# pc_healthypi_move_sensor_dual_v1.net
KiCad netlist of a schematic drawn in EAGLE
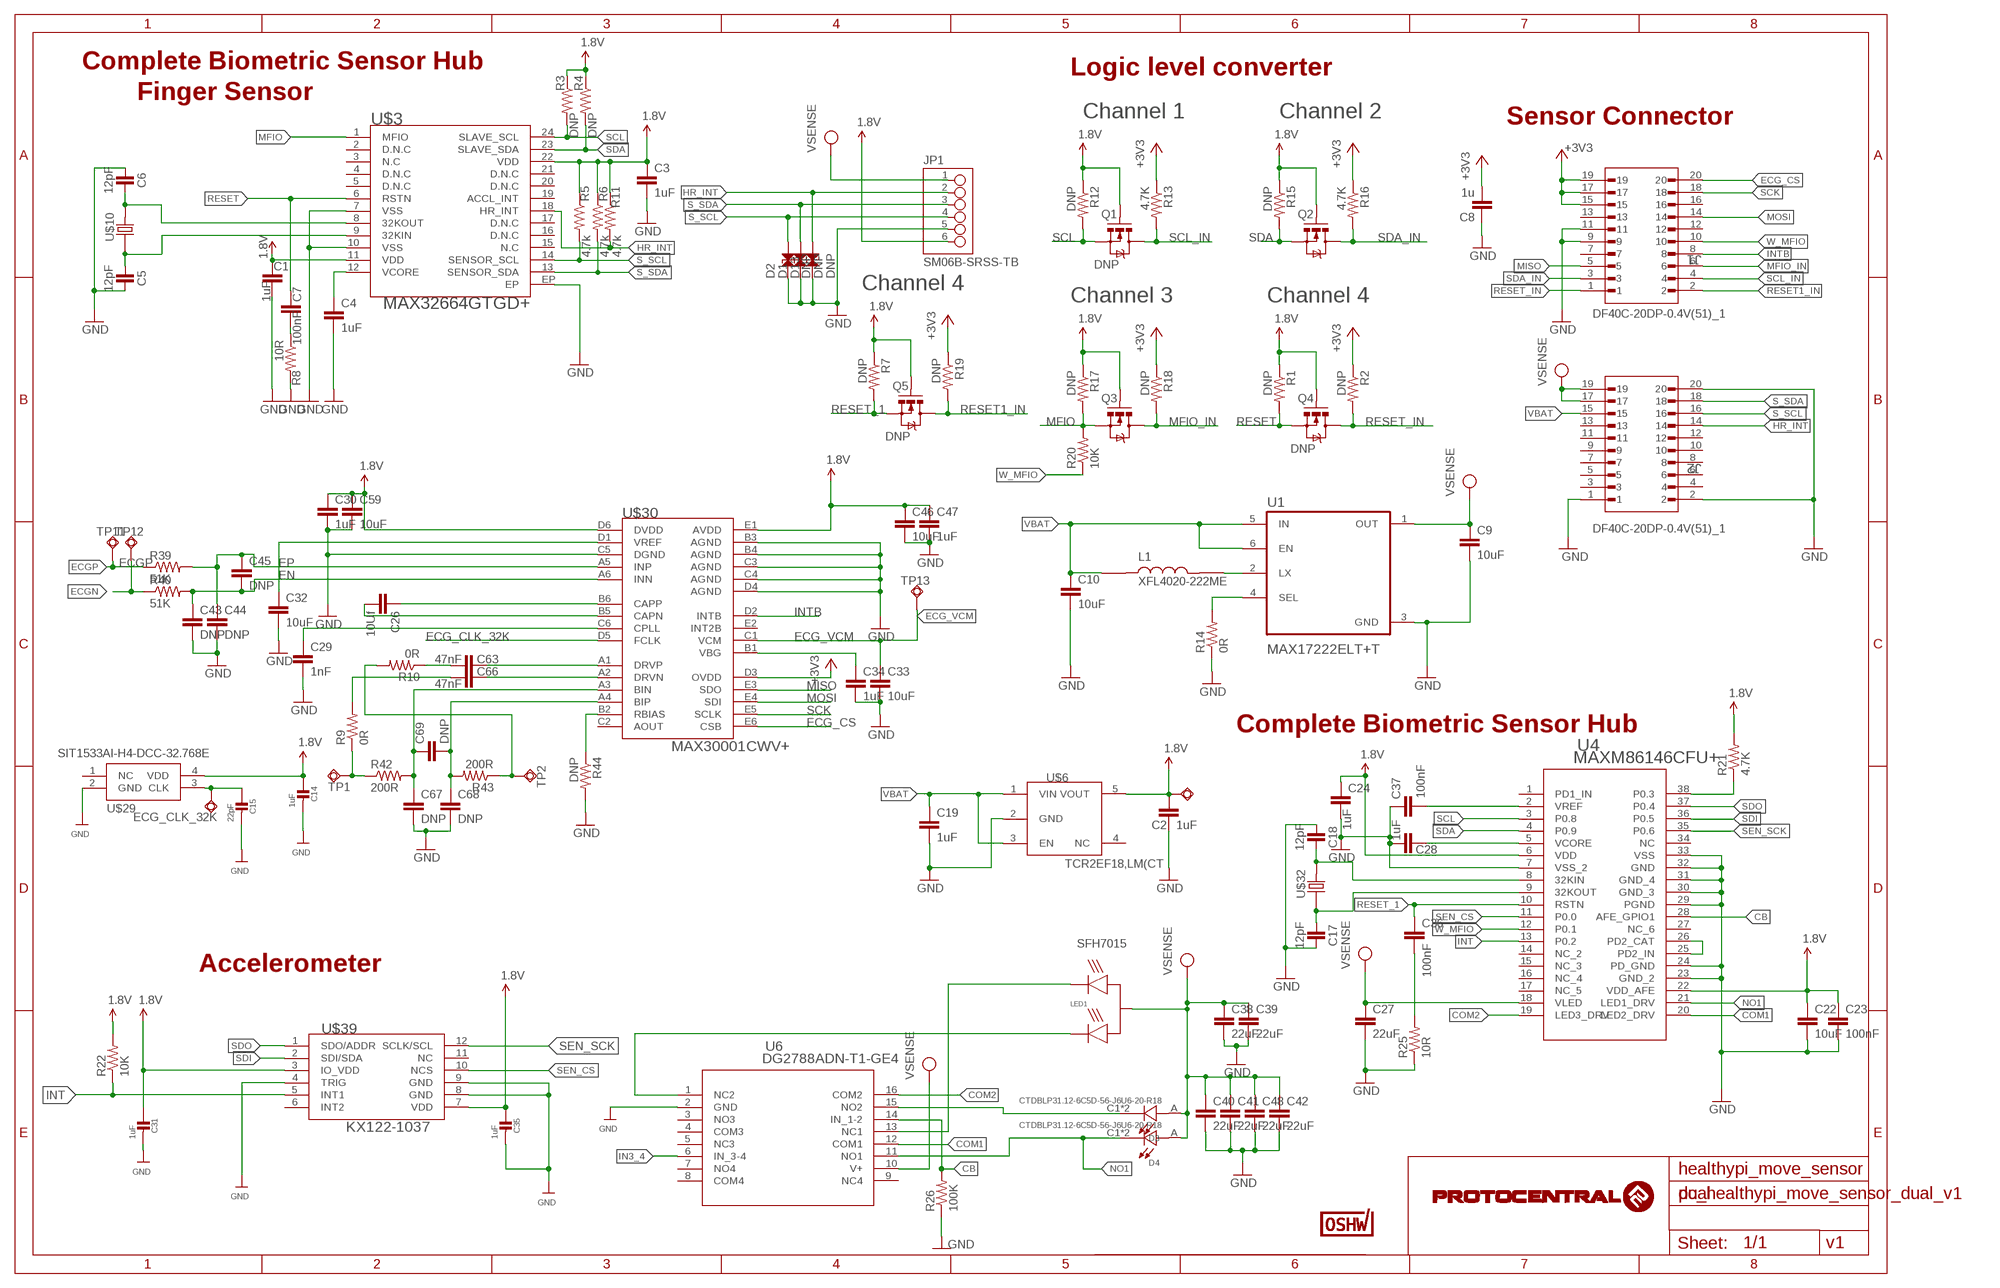
[diagram p0: schematic, sheet 1]

(export (version "E")
  (design (tool "Eeschema 10.0.6"))
  (components
    (comp (ref "C1")
      (value "1uF")
      (footprint "eagle-import:C0402")
      (libsource (lib "eagle-import") (part "C-EUC0402"))
    )
    (comp (ref "C2")
      (value "1uF")
      (footprint "eagle-import:C0402")
      (libsource (lib "eagle-import") (part "C-EUC0402"))
    )
    (comp (ref "C3")
      (value "1uF")
      (footprint "eagle-import:C0402")
      (libsource (lib "eagle-import") (part "C-EUC0402"))
    )
    (comp (ref "C4")
      (value "1uF")
      (footprint "eagle-import:C0402")
      (libsource (lib "eagle-import") (part "C-EUC0402"))
    )
    (comp (ref "C5")
      (value "12pF")
      (footprint "eagle-import:C0402")
      (libsource (lib "eagle-import") (part "CAPACITORS-0402"))
    )
    (comp (ref "C6")
      (value "12pF")
      (footprint "eagle-import:C0402")
      (libsource (lib "eagle-import") (part "CAPACITORS-0402"))
    )
    (comp (ref "C7")
      (value "100nF")
      (footprint "eagle-import:C0402")
      (libsource (lib "eagle-import") (part "C-EUC0402"))
    )
    (comp (ref "C8")
      (value "1u")
      (footprint "eagle-import:C0402")
      (libsource (lib "eagle-import") (part "C-EUC0402"))
    )
    (comp (ref "C9")
      (value "10uF")
      (footprint "eagle-import:C0402")
      (libsource (lib "eagle-import") (part "C-EUC0402"))
    )
    (comp (ref "C10")
      (value "10uF")
      (footprint "eagle-import:C0402")
      (libsource (lib "eagle-import") (part "C-EUC0402"))
    )
    (comp (ref "C14")
      (value "1uF")
      (footprint "eagle-import:0402")
      (libsource (lib "eagle-import") (part "CAP_CERAMIC0402"))
    )
    (comp (ref "C15")
      (value "22pF")
      (footprint "eagle-import:0402")
      (libsource (lib "eagle-import") (part "CAP_CERAMIC0402"))
    )
    (comp (ref "C17")
      (value "12pF")
      (footprint "eagle-import:C0402")
      (libsource (lib "eagle-import") (part "CAPACITORS-0402"))
    )
    (comp (ref "C18")
      (value "12pF")
      (footprint "eagle-import:C0402")
      (libsource (lib "eagle-import") (part "CAPACITORS-0402"))
    )
    (comp (ref "C19")
      (value "1uF")
      (footprint "eagle-import:C0402")
      (libsource (lib "eagle-import") (part "C-EUC0402"))
    )
    (comp (ref "C22")
      (value "10uF")
      (footprint "eagle-import:C0402")
      (libsource (lib "eagle-import") (part "C-EUC0402"))
    )
    (comp (ref "C23")
      (value "100nF")
      (footprint "eagle-import:C0402")
      (libsource (lib "eagle-import") (part "C-EUC0402"))
    )
    (comp (ref "C24")
      (value "1uF")
      (footprint "eagle-import:C0402")
      (libsource (lib "eagle-import") (part "C-EUC0402"))
    )
    (comp (ref "C26")
      (value "10Uf")
      (footprint "eagle-import:C0402")
      (libsource (lib "eagle-import") (part "C-EUC0402"))
    )
    (comp (ref "C27")
      (value "22uF")
      (footprint "eagle-import:C0805")
      (libsource (lib "eagle-import") (part "C-EUC0805"))
    )
    (comp (ref "C28")
      (value "1uF")
      (footprint "eagle-import:C0402")
      (libsource (lib "eagle-import") (part "C-EUC0402"))
    )
    (comp (ref "C29")
      (value "1nF")
      (footprint "eagle-import:C0402")
      (libsource (lib "eagle-import") (part "C-EUC0402"))
    )
    (comp (ref "C30")
      (value "1uF")
      (footprint "eagle-import:C0402")
      (libsource (lib "eagle-import") (part "C-EUC0402"))
    )
    (comp (ref "C31")
      (value "1uF")
      (footprint "eagle-import:0402")
      (libsource (lib "eagle-import") (part "CAP_CERAMIC0402"))
    )
    (comp (ref "C32")
      (value "10uF")
      (footprint "eagle-import:C0402")
      (libsource (lib "eagle-import") (part "C-EUC0402"))
    )
    (comp (ref "C33")
      (value "10uF")
      (footprint "eagle-import:C0402")
      (libsource (lib "eagle-import") (part "C-EUC0402"))
    )
    (comp (ref "C34")
      (value "1uF")
      (footprint "eagle-import:C0402")
      (libsource (lib "eagle-import") (part "C-EUC0402"))
    )
    (comp (ref "C35")
      (value "1uF")
      (footprint "eagle-import:0402")
      (libsource (lib "eagle-import") (part "CAP_CERAMIC0402"))
    )
    (comp (ref "C36")
      (value "100nF")
      (footprint "eagle-import:C0402")
      (libsource (lib "eagle-import") (part "C-EUC0402"))
    )
    (comp (ref "C37")
      (value "100nF")
      (footprint "eagle-import:C0402")
      (libsource (lib "eagle-import") (part "C-EUC0402"))
    )
    (comp (ref "C38")
      (value "22uF")
      (footprint "eagle-import:C0805")
      (libsource (lib "eagle-import") (part "C-EUC0805"))
    )
    (comp (ref "C39")
      (value "22uF")
      (footprint "eagle-import:C0805")
      (libsource (lib "eagle-import") (part "C-EUC0805"))
    )
    (comp (ref "C40")
      (value "22uF")
      (footprint "eagle-import:C0805")
      (libsource (lib "eagle-import") (part "C-EUC0805"))
    )
    (comp (ref "C41")
      (value "22uF")
      (footprint "eagle-import:C0805")
      (libsource (lib "eagle-import") (part "C-EUC0805"))
    )
    (comp (ref "C42")
      (value "22uF")
      (footprint "eagle-import:C0805")
      (libsource (lib "eagle-import") (part "C-EUC0805"))
    )
    (comp (ref "C43")
      (value "DNP")
      (footprint "eagle-import:C0402")
      (libsource (lib "eagle-import") (part "C-EUC0402"))
    )
    (comp (ref "C44")
      (value "DNP")
      (footprint "eagle-import:C0402")
      (libsource (lib "eagle-import") (part "C-EUC0402"))
    )
    (comp (ref "C45")
      (value "DNP")
      (footprint "eagle-import:C0402")
      (libsource (lib "eagle-import") (part "C-EUC0402"))
    )
    (comp (ref "C46")
      (value "10uF")
      (footprint "eagle-import:C0402")
      (libsource (lib "eagle-import") (part "C-EUC0402"))
    )
    (comp (ref "C47")
      (value "1uF")
      (footprint "eagle-import:C0402")
      (libsource (lib "eagle-import") (part "C-EUC0402"))
    )
    (comp (ref "C48")
      (value "22uF")
      (footprint "eagle-import:C0805")
      (libsource (lib "eagle-import") (part "C-EUC0805"))
    )
    (comp (ref "C59")
      (value "10uF")
      (footprint "eagle-import:C0402")
      (libsource (lib "eagle-import") (part "C-EUC0402"))
    )
    (comp (ref "C63")
      (value "47nF")
      (footprint "eagle-import:C0402")
      (libsource (lib "eagle-import") (part "C-EUC0402"))
    )
    (comp (ref "C66")
      (value "47nF")
      (footprint "eagle-import:C0402")
      (libsource (lib "eagle-import") (part "C-EUC0402"))
    )
    (comp (ref "C67")
      (value "DNP")
      (footprint "eagle-import:C0402")
      (libsource (lib "eagle-import") (part "C-EUC0402"))
    )
    (comp (ref "C68")
      (value "DNP")
      (footprint "eagle-import:C0402")
      (libsource (lib "eagle-import") (part "C-EUC0402"))
    )
    (comp (ref "C69")
      (value "DNP")
      (footprint "eagle-import:C0402")
      (libsource (lib "eagle-import") (part "C-EUC0402"))
    )
    (comp (ref "D1")
      (value "DNP")
      (footprint "eagle-import:0402")
      (fields
        (field (name "DIGIKEY_PART") "PESD0402-140CT-ND")
        (field (name "MOUSE_PART") "650-PESD0402-140")
      )
      (libsource (lib "eagle-import") (part "PESD0402-0402"))
    )
    (comp (ref "D2")
      (value "DNP")
      (footprint "eagle-import:0402")
      (fields
        (field (name "DIGIKEY_PART") "PESD0402-140CT-ND")
        (field (name "MOUSE_PART") "650-PESD0402-140")
      )
      (libsource (lib "eagle-import") (part "PESD0402-0402"))
    )
    (comp (ref "D3")
      (value "CTDBLP31.12-6C5D-56-J6U6-20-R18")
      (footprint "eagle-import:LED_CTDBLP31.12-6C5D-56-J6U6-20-R18")
      (fields
        (field (name "MF") "OSRAM Opto Semiconductors")
        (field (name "MP") "CT DBLP31.12-6C5D-56-J6U6-20-R18")
      )
      (libsource (lib "eagle-import") (part "CTDBLP31.12-6C5D-56-J6U6-20-R18"))
    )
    (comp (ref "D4")
      (value "CTDBLP31.12-6C5D-56-J6U6-20-R18")
      (footprint "eagle-import:LED_CTDBLP31.12-6C5D-56-J6U6-20-R18")
      (fields
        (field (name "MF") "OSRAM Opto Semiconductors")
        (field (name "MP") "CT DBLP31.12-6C5D-56-J6U6-20-R18")
      )
      (libsource (lib "eagle-import") (part "CTDBLP31.12-6C5D-56-J6U6-20-R18"))
    )
    (comp (ref "D13")
      (value "DNP")
      (footprint "eagle-import:0402")
      (fields
        (field (name "DIGIKEY_PART") "PESD0402-140CT-ND")
        (field (name "MOUSE_PART") "650-PESD0402-140")
      )
      (libsource (lib "eagle-import") (part "PESD0402-0402"))
    )
    (comp (ref "J1")
      (value "DF40C-20DP-0.4V(51)_1")
      (footprint "eagle-import:HRS_DF40C-20DP-0.4V(51)")
      (fields (field (name "MANUFACTURER") "Hirose Electric"))
      (libsource (lib "eagle-import") (part "DF40C-20DP-0.4V(51)_1"))
    )
    (comp (ref "J2")
      (value "DF40C-20DP-0.4V(51)_1")
      (footprint "eagle-import:HRS_DF40C-20DP-0.4V(51)")
      (fields (field (name "MANUFACTURER") "Hirose Electric"))
      (libsource (lib "eagle-import") (part "DF40C-20DP-0.4V(51)_1"))
    )
    (comp (ref "JP1")
      (value "SM06B-SRSS-TB")
      (footprint "eagle-import:SM06B-SRSS-TB")
      (fields (field (name "MF") "JST Sales"))
      (libsource (lib "eagle-import") (part "SM06B-SRSS-TB"))
    )
    (comp (ref "L1")
      (value "XFL4020-222ME")
      (footprint "eagle-import:IND_XFL4020-222ME")
      (fields (field (name "MF") "Coilcraft"))
      (libsource (lib "eagle-import") (part "XFL4020-222ME"))
    )
    (comp (ref "LED1")
      (value "SFH7015")
      (footprint "eagle-import:SFH7015")
      (fields (field (name "MF") "OSRAM Opto Semiconductors") (field (name "MP") "SFH 7015"))
      (libsource (lib "eagle-import") (part "SFH7015"))
    )
    (comp (ref "Q1")
      (value "DNP")
      (footprint "eagle-import:SOT23-3")
      (libsource (lib "eagle-import") (part "MOSFET-NCHANNELSMD"))
    )
    (comp (ref "Q2")
      (value "DNP")
      (footprint "eagle-import:SOT23-3")
      (libsource (lib "eagle-import") (part "MOSFET-NCHANNELSMD"))
    )
    (comp (ref "Q3")
      (value "DNP")
      (footprint "eagle-import:SOT23-3")
      (libsource (lib "eagle-import") (part "MOSFET-NCHANNELSMD"))
    )
    (comp (ref "Q4")
      (value "DNP")
      (footprint "eagle-import:SOT23-3")
      (libsource (lib "eagle-import") (part "MOSFET-NCHANNELSMD"))
    )
    (comp (ref "Q5")
      (value "DNP")
      (footprint "eagle-import:SOT23-3")
      (libsource (lib "eagle-import") (part "MOSFET-NCHANNELSMD"))
    )
    (comp (ref "R1")
      (value "DNP")
      (footprint "eagle-import:0402-RES")
      (libsource (lib "eagle-import") (part "RESISTOR0402-RES"))
    )
    (comp (ref "R2")
      (value "DNP")
      (footprint "eagle-import:0402-RES")
      (libsource (lib "eagle-import") (part "RESISTOR0402-RES"))
    )
    (comp (ref "R3")
      (value "DNP")
      (footprint "eagle-import:0402-RES")
      (libsource (lib "eagle-import") (part "RESISTOR0402-RES"))
    )
    (comp (ref "R4")
      (value "DNP")
      (footprint "eagle-import:0402-RES")
      (libsource (lib "eagle-import") (part "RESISTOR0402-RES"))
    )
    (comp (ref "R5")
      (value "4.7k")
      (footprint "eagle-import:0402-RES")
      (libsource (lib "eagle-import") (part "RESISTOR0402-RES"))
    )
    (comp (ref "R6")
      (value "4.7k")
      (footprint "eagle-import:0402-RES")
      (libsource (lib "eagle-import") (part "RESISTOR0402-RES"))
    )
    (comp (ref "R7")
      (value "DNP")
      (footprint "eagle-import:0402-RES")
      (libsource (lib "eagle-import") (part "RESISTOR0402-RES"))
    )
    (comp (ref "R8")
      (value "10R")
      (footprint "eagle-import:0402-RES")
      (libsource (lib "eagle-import") (part "RESISTOR0402-RES"))
    )
    (comp (ref "R9")
      (value "0R")
      (footprint "eagle-import:0402-RES")
      (libsource (lib "eagle-import") (part "RESISTOR0402-RES"))
    )
    (comp (ref "R10")
      (value "0R")
      (footprint "eagle-import:0402-RES")
      (libsource (lib "eagle-import") (part "RESISTOR0402-RES"))
    )
    (comp (ref "R11")
      (value "4.7k")
      (footprint "eagle-import:0402-RES")
      (libsource (lib "eagle-import") (part "RESISTOR0402-RES"))
    )
    (comp (ref "R12")
      (value "DNP")
      (footprint "eagle-import:0402-RES")
      (libsource (lib "eagle-import") (part "RESISTOR0402-RES"))
    )
    (comp (ref "R13")
      (value "4.7K")
      (footprint "eagle-import:0402-RES")
      (libsource (lib "eagle-import") (part "RESISTOR0402-RES"))
    )
    (comp (ref "R14")
      (value "0R")
      (footprint "eagle-import:R0402")
      (libsource (lib "eagle-import") (part "R-US_R0402"))
    )
    (comp (ref "R15")
      (value "DNP")
      (footprint "eagle-import:0402-RES")
      (libsource (lib "eagle-import") (part "RESISTOR0402-RES"))
    )
    (comp (ref "R16")
      (value "4.7K")
      (footprint "eagle-import:0402-RES")
      (libsource (lib "eagle-import") (part "RESISTOR0402-RES"))
    )
    (comp (ref "R17")
      (value "DNP")
      (footprint "eagle-import:0402-RES")
      (libsource (lib "eagle-import") (part "RESISTOR0402-RES"))
    )
    (comp (ref "R18")
      (value "DNP")
      (footprint "eagle-import:0402-RES")
      (libsource (lib "eagle-import") (part "RESISTOR0402-RES"))
    )
    (comp (ref "R19")
      (value "DNP")
      (footprint "eagle-import:0402-RES")
      (libsource (lib "eagle-import") (part "RESISTOR0402-RES"))
    )
    (comp (ref "R20")
      (value "10K")
      (footprint "eagle-import:0402-RES")
      (libsource (lib "eagle-import") (part "RESISTOR0402-RES"))
    )
    (comp (ref "R21")
      (value "4.7K")
      (footprint "eagle-import:R0402")
      (libsource (lib "eagle-import") (part "R-US_R0402"))
    )
    (comp (ref "R22")
      (value "10K")
      (footprint "eagle-import:0402-RES")
      (libsource (lib "eagle-import") (part "RESISTOR0402-RES"))
    )
    (comp (ref "R25")
      (value "10R")
      (footprint "eagle-import:R0402")
      (libsource (lib "eagle-import") (part "R-US_R0402"))
    )
    (comp (ref "R26")
      (value "100K")
      (footprint "eagle-import:R0402")
      (libsource (lib "eagle-import") (part "R-US_R0402"))
    )
    (comp (ref "R39")
      (value "51K")
      (footprint "eagle-import:0402-RES")
      (libsource (lib "eagle-import") (part "RESISTOR0402-RES"))
    )
    (comp (ref "R40")
      (value "51K")
      (footprint "eagle-import:0402-RES")
      (libsource (lib "eagle-import") (part "RESISTOR0402-RES"))
    )
    (comp (ref "R42")
      (value "200R")
      (footprint "eagle-import:0402-RES")
      (libsource (lib "eagle-import") (part "RESISTOR0402-RES"))
    )
    (comp (ref "R43")
      (value "200R")
      (footprint "eagle-import:0402-RES")
      (libsource (lib "eagle-import") (part "RESISTOR0402-RES"))
    )
    (comp (ref "R44")
      (value "DNP")
      (footprint "eagle-import:0402-RES")
      (libsource (lib "eagle-import") (part "RESISTOR0402-RES"))
    )
    (comp (ref "SWIO1")
      (value "TPSQTP11R")
      (footprint "eagle-import:TP11R")
      (libsource (lib "eagle-import") (part "TPSQTP11R"))
    )
    (comp (ref "SWIO5")
      (value "TPSQTP11R")
      (footprint "eagle-import:TP11R")
      (libsource (lib "eagle-import") (part "TPSQTP11R"))
    )
    (comp (ref "TP1")
      (value "TPSQTP20SQ")
      (footprint "eagle-import:TP20SQ")
      (libsource (lib "eagle-import") (part "TPSQTP20SQ"))
    )
    (comp (ref "TP2")
      (value "TPSQTP20SQ")
      (footprint "eagle-import:TP20SQ")
      (libsource (lib "eagle-import") (part "TPSQTP20SQ"))
    )
    (comp (ref "TP11")
      (value "TPSQTP20SQ")
      (footprint "eagle-import:TP20SQ")
      (libsource (lib "eagle-import") (part "TPSQTP20SQ"))
    )
    (comp (ref "TP12")
      (value "TPSQTP20SQ")
      (footprint "eagle-import:TP20SQ")
      (libsource (lib "eagle-import") (part "TPSQTP20SQ"))
    )
    (comp (ref "TP13")
      (value "TPSQTP20SQ")
      (footprint "eagle-import:TP20SQ")
      (libsource (lib "eagle-import") (part "TPSQTP20SQ"))
    )
    (comp (ref "U$3")
      (value "MAX32664GTGD+")
      (footprint "eagle-import:TQFN-24L")
      (libsource (lib "eagle-import") (part "MAX32664GTGA+"))
    )
    (comp (ref "U$6")
      (value "TCR2EF18,LM(CT")
      (footprint "eagle-import:SOT95P285X140-5N")
      (libsource (lib "eagle-import") (part "AP7354D-18W5-7"))
    )
    (comp (ref "U$10")
      (value "520-327-12.5-34B(32.768KHZ)")
      (footprint "eagle-import:ECX-31B")
      (libsource (lib "eagle-import") (part "ECS-X-34B"))
    )
    (comp (ref "U$29")
      (value "SIT1533AI-H4-DCC-32.768E")
      (footprint "eagle-import:SIT1533")
      (libsource (lib "eagle-import") (part "SIT1533AI-H4-DCC-32.768E"))
    )
    (comp (ref "U$30")
      (value "MAX30001CWV+")
      (footprint "eagle-import:30WLP")
      (libsource (lib "eagle-import") (part "MAX30001CWV+"))
    )
    (comp (ref "U$32")
      (value "520-327-12.5-34B(32.768KHZ)")
      (footprint "eagle-import:ECX-31B")
      (libsource (lib "eagle-import") (part "ECS-X-34B"))
    )
    (comp (ref "U$39")
      (value "KX122-1037")
      (footprint "eagle-import:KIONIX_KXTJ3-1057")
      (libsource (lib "eagle-import") (part "KX122-1037"))
    )
    (comp (ref "U$48")
      (value "CERT-SMALL")
      (footprint "eagle-import:CERT-SMALL-SILK")
      (libsource (lib "eagle-import") (part "CERT-SMALL"))
    )
    (comp (ref "U1")
      (value "MAX17222ELT+T")
      (footprint "eagle-import:SON65P200X200X80-6N")
      (fields (field (name "MF") "Analog Devices"))
      (libsource (lib "eagle-import") (part "MAX17222ELT+T"))
    )
    (comp (ref "U4")
      (value "MAXM86146CFU+")
      (footprint "eagle-import:21-100323A_90-100112A_MXM")
      (fields (field (name "COPYRIGHT") "Copyright (C) 2023 Ultra Librarian. All rights reserved."))
      (libsource (lib "eagle-import") (part "MAXM86146CFU+"))
    )
    (comp (ref "U6")
      (value "DG2788ADN-T1-GE4")
      (footprint "eagle-import:MINIQFN-16_VIS")
      (fields (field (name "COPYRIGHT") "Copyright (C) 2023 Ultra Librarian. All rights reserved."))
      (libsource (lib "eagle-import") (part "DG2788ADN-T1-GE4"))
    )
  )
  (nets
    (net (code "1") (name "+3V3") (class "Default")
      (node (ref "C8") (pin "2") (pinfunction "2_2") (pintype "passive"))
      (node (ref "J1") (pin "15") (pinfunction "15_15") (pintype "passive"))
      (node (ref "J1") (pin "17") (pinfunction "17_17") (pintype "passive"))
      (node (ref "J1") (pin "19") (pinfunction "19_19") (pintype "passive"))
      (node (ref "R13") (pin "1") (pinfunction "1_1") (pintype "passive"))
      (node (ref "R16") (pin "1") (pinfunction "1_1") (pintype "passive"))
      (node (ref "R18") (pin "1") (pinfunction "1_1") (pintype "passive"))
      (node (ref "R19") (pin "1") (pinfunction "1_1") (pintype "passive"))
      (node (ref "R2") (pin "1") (pinfunction "1_1") (pintype "passive"))
      (node (ref "U$30") (pin "D3") (pinfunction "OVDD_D3") (pintype "bidirectional"))
    )
    (net (code "2") (name "/ECG_CLK_32K") (class "Default")
      (node (ref "C15") (pin "1") (pinfunction "P$1_1") (pintype "passive"))
      (node (ref "SWIO1") (pin "TP") (pinfunction "TP_TP") (pintype "input"))
      (node (ref "U$29") (pin "3") (pinfunction "CLK_3") (pintype "bidirectional"))
      (node (ref "U$30") (pin "D5") (pinfunction "FCLK_D5") (pintype "bidirectional"))
    )
    (net (code "3") (name "/EN") (class "Default")
      (node (ref "C43") (pin "1") (pinfunction "1_1") (pintype "passive"))
      (node (ref "C45") (pin "2") (pinfunction "2_2") (pintype "passive"))
      (node (ref "R40") (pin "2") (pinfunction "2_2") (pintype "passive"))
      (node (ref "U$30") (pin "A6") (pinfunction "INN_A6") (pintype "bidirectional"))
    )
    (net (code "4") (name "/EP") (class "Default")
      (node (ref "C44") (pin "1") (pinfunction "1_1") (pintype "passive"))
      (node (ref "C45") (pin "1") (pinfunction "1_1") (pintype "passive"))
      (node (ref "R39") (pin "2") (pinfunction "2_2") (pintype "passive"))
      (node (ref "U$30") (pin "A5") (pinfunction "INP_A5") (pintype "bidirectional"))
    )
    (net (code "5") (name "1.8V") (class "Default")
      (node (ref "C1") (pin "1") (pinfunction "1_1") (pintype "passive"))
      (node (ref "C14") (pin "1") (pinfunction "P$1_1") (pintype "passive"))
      (node (ref "C2") (pin "1") (pinfunction "1_1") (pintype "passive"))
      (node (ref "C22") (pin "1") (pinfunction "1_1") (pintype "passive"))
      (node (ref "C23") (pin "1") (pinfunction "1_1") (pintype "passive"))
      (node (ref "C24") (pin "1") (pinfunction "1_1") (pintype "passive"))
      (node (ref "C3") (pin "1") (pinfunction "1_1") (pintype "passive"))
      (node (ref "C30") (pin "1") (pinfunction "1_1") (pintype "passive"))
      (node (ref "C31") (pin "1") (pinfunction "P$1_1") (pintype "passive"))
      (node (ref "C35") (pin "1") (pinfunction "P$1_1") (pintype "passive"))
      (node (ref "C46") (pin "1") (pinfunction "1_1") (pintype "passive"))
      (node (ref "C47") (pin "1") (pinfunction "1_1") (pintype "passive"))
      (node (ref "C59") (pin "1") (pinfunction "1_1") (pintype "passive"))
      (node (ref "JP1") (pin "6") (pinfunction "P$6_6") (pintype "bidirectional"))
      (node (ref "Q1") (pin "1") (pinfunction "G_1") (pintype "passive"))
      (node (ref "Q2") (pin "1") (pinfunction "G_1") (pintype "passive"))
      (node (ref "Q3") (pin "1") (pinfunction "G_1") (pintype "passive"))
      (node (ref "Q4") (pin "1") (pinfunction "G_1") (pintype "passive"))
      (node (ref "Q5") (pin "1") (pinfunction "G_1") (pintype "passive"))
      (node (ref "R1") (pin "1") (pinfunction "1_1") (pintype "passive"))
      (node (ref "R11") (pin "1") (pinfunction "1_1") (pintype "passive"))
      (node (ref "R12") (pin "1") (pinfunction "1_1") (pintype "passive"))
      (node (ref "R15") (pin "1") (pinfunction "1_1") (pintype "passive"))
      (node (ref "R17") (pin "1") (pinfunction "1_1") (pintype "passive"))
      (node (ref "R21") (pin "2") (pinfunction "2_2") (pintype "passive"))
      (node (ref "R22") (pin "2") (pinfunction "2_2") (pintype "passive"))
      (node (ref "R3") (pin "1") (pinfunction "1_1") (pintype "passive"))
      (node (ref "R4") (pin "1") (pinfunction "1_1") (pintype "passive"))
      (node (ref "R5") (pin "1") (pinfunction "1_1") (pintype "passive"))
      (node (ref "R6") (pin "1") (pinfunction "1_1") (pintype "passive"))
      (node (ref "R7") (pin "1") (pinfunction "1_1") (pintype "passive"))
      (node (ref "SWIO5") (pin "TP") (pinfunction "TP_TP") (pintype "input"))
      (node (ref "U$29") (pin "4") (pinfunction "VDD_4") (pintype "bidirectional"))
      (node (ref "U$3") (pin "11") (pinfunction "VDD_11") (pintype "bidirectional"))
      (node (ref "U$3") (pin "22") (pinfunction "VDD_22") (pintype "bidirectional"))
      (node (ref "U$30") (pin "D6") (pinfunction "DVDD_D6") (pintype "bidirectional"))
      (node (ref "U$30") (pin "E1") (pinfunction "AVDD_E1") (pintype "bidirectional"))
      (node (ref "U$39") (pin "3") (pinfunction "IO_VDD_3") (pintype "bidirectional"))
      (node (ref "U$39") (pin "7") (pinfunction "VDD_7") (pintype "bidirectional"))
      (node (ref "U$6") (pin "5") (pinfunction "VOUT_5") (pintype "bidirectional"))
      (node (ref "U4") (pin "22") (pinfunction "VDD_AFE_22") (pintype "input"))
      (node (ref "U4") (pin "6") (pinfunction "VDD_6") (pintype "power_in"))
    )
    (net (code "6") (name "CB") (class "Default")
      (node (ref "R26") (pin "2") (pinfunction "2_2") (pintype "passive"))
      (node (ref "U4") (pin "28") (pinfunction "AFE_GPIO1_28") (pintype "bidirectional"))
      (node (ref "U6") (pin "14") (pinfunction "IN_1-2_14") (pintype "bidirectional"))
    )
    (net (code "7") (name "COM1") (class "Default")
      (node (ref "U4") (pin "20") (pinfunction "LED2_DRV_20") (pintype "output"))
      (node (ref "U6") (pin "12") (pinfunction "COM1_12") (pintype "bidirectional"))
    )
    (net (code "8") (name "COM2") (class "Default")
      (node (ref "U4") (pin "19") (pinfunction "LED3_DRV_19") (pintype "output"))
      (node (ref "U6") (pin "16") (pinfunction "COM2_16") (pintype "bidirectional"))
    )
    (net (code "9") (name "ECGN") (class "Default")
      (node (ref "R40") (pin "1") (pinfunction "1_1") (pintype "passive"))
      (node (ref "TP12") (pin "TP") (pinfunction "TP_TP") (pintype "input"))
    )
    (net (code "10") (name "ECGP") (class "Default")
      (node (ref "R39") (pin "1") (pinfunction "1_1") (pintype "passive"))
      (node (ref "TP11") (pin "TP") (pinfunction "TP_TP") (pintype "input"))
    )
    (net (code "11") (name "ECG_CS") (class "Default")
      (node (ref "J1") (pin "20") (pinfunction "20_20") (pintype "passive"))
      (node (ref "U$30") (pin "E6") (pinfunction "CSB_E6") (pintype "bidirectional"))
    )
    (net (code "12") (name "ECG_VCM") (class "Default")
      (node (ref "C33") (pin "1") (pinfunction "1_1") (pintype "passive"))
      (node (ref "TP13") (pin "TP") (pinfunction "TP_TP") (pintype "input"))
      (node (ref "U$30") (pin "C1") (pinfunction "VCM_C1") (pintype "bidirectional"))
    )
    (net (code "13") (name "GND") (class "Default")
      (node (ref "C1") (pin "2") (pinfunction "2_2") (pintype "passive"))
      (node (ref "C10") (pin "2") (pinfunction "2_2") (pintype "passive"))
      (node (ref "C14") (pin "2") (pinfunction "P$2_2") (pintype "passive"))
      (node (ref "C15") (pin "2") (pinfunction "P$2_2") (pintype "passive"))
      (node (ref "C17") (pin "2") (pinfunction "2_2") (pintype "passive"))
      (node (ref "C18") (pin "1") (pinfunction "1_1") (pintype "passive"))
      (node (ref "C19") (pin "2") (pinfunction "2_2") (pintype "passive"))
      (node (ref "C2") (pin "2") (pinfunction "2_2") (pintype "passive"))
      (node (ref "C22") (pin "2") (pinfunction "2_2") (pintype "passive"))
      (node (ref "C23") (pin "2") (pinfunction "2_2") (pintype "passive"))
      (node (ref "C24") (pin "2") (pinfunction "2_2") (pintype "passive"))
      (node (ref "C27") (pin "2") (pinfunction "2_2") (pintype "passive"))
      (node (ref "C28") (pin "2") (pinfunction "2_2") (pintype "passive"))
      (node (ref "C29") (pin "2") (pinfunction "2_2") (pintype "passive"))
      (node (ref "C3") (pin "2") (pinfunction "2_2") (pintype "passive"))
      (node (ref "C30") (pin "2") (pinfunction "2_2") (pintype "passive"))
      (node (ref "C31") (pin "2") (pinfunction "P$2_2") (pintype "passive"))
      (node (ref "C32") (pin "2") (pinfunction "2_2") (pintype "passive"))
      (node (ref "C33") (pin "2") (pinfunction "2_2") (pintype "passive"))
      (node (ref "C34") (pin "2") (pinfunction "2_2") (pintype "passive"))
      (node (ref "C35") (pin "2") (pinfunction "P$2_2") (pintype "passive"))
      (node (ref "C37") (pin "1") (pinfunction "1_1") (pintype "passive"))
      (node (ref "C38") (pin "2") (pinfunction "2_2") (pintype "passive"))
      (node (ref "C39") (pin "2") (pinfunction "2_2") (pintype "passive"))
      (node (ref "C4") (pin "2") (pinfunction "2_2") (pintype "passive"))
      (node (ref "C40") (pin "2") (pinfunction "2_2") (pintype "passive"))
      (node (ref "C41") (pin "2") (pinfunction "2_2") (pintype "passive"))
      (node (ref "C42") (pin "2") (pinfunction "2_2") (pintype "passive"))
      (node (ref "C43") (pin "2") (pinfunction "2_2") (pintype "passive"))
      (node (ref "C44") (pin "2") (pinfunction "2_2") (pintype "passive"))
      (node (ref "C46") (pin "2") (pinfunction "2_2") (pintype "passive"))
      (node (ref "C47") (pin "2") (pinfunction "2_2") (pintype "passive"))
      (node (ref "C48") (pin "2") (pinfunction "2_2") (pintype "passive"))
      (node (ref "C5") (pin "2") (pinfunction "2_2") (pintype "passive"))
      (node (ref "C59") (pin "2") (pinfunction "2_2") (pintype "passive"))
      (node (ref "C6") (pin "1") (pinfunction "1_1") (pintype "passive"))
      (node (ref "C67") (pin "2") (pinfunction "2_2") (pintype "passive"))
      (node (ref "C68") (pin "2") (pinfunction "2_2") (pintype "passive"))
      (node (ref "C8") (pin "1") (pinfunction "1_1") (pintype "passive"))
      (node (ref "C9") (pin "2") (pinfunction "2_2") (pintype "passive"))
      (node (ref "D1") (pin "1") (pinfunction "1_1") (pintype "bidirectional"))
      (node (ref "D13") (pin "1") (pinfunction "1_1") (pintype "bidirectional"))
      (node (ref "D2") (pin "1") (pinfunction "1_1") (pintype "bidirectional"))
      (node (ref "J1") (pin "11") (pinfunction "11_11") (pintype "passive"))
      (node (ref "J1") (pin "9") (pinfunction "9_9") (pintype "passive"))
      (node (ref "J2") (pin "1") (pinfunction "1_1") (pintype "passive"))
      (node (ref "J2") (pin "2") (pinfunction "2_2") (pintype "passive"))
      (node (ref "J2") (pin "20") (pinfunction "20_20") (pintype "passive"))
      (node (ref "JP1") (pin "5") (pinfunction "P$5_5") (pintype "bidirectional"))
      (node (ref "R14") (pin "1") (pinfunction "1_1") (pintype "passive"))
      (node (ref "R25") (pin "1") (pinfunction "1_1") (pintype "passive"))
      (node (ref "R26") (pin "1") (pinfunction "1_1") (pintype "passive"))
      (node (ref "R44") (pin "2") (pinfunction "2_2") (pintype "passive"))
      (node (ref "R8") (pin "2") (pinfunction "2_2") (pintype "passive"))
      (node (ref "U$29") (pin "2") (pinfunction "GND_2") (pintype "bidirectional"))
      (node (ref "U$3") (pin "10") (pinfunction "VSS_10") (pintype "bidirectional"))
      (node (ref "U$3") (pin "7") (pinfunction "VSS_7") (pintype "bidirectional"))
      (node (ref "U$3") (pin "EP") (pinfunction "EP_EP") (pintype "bidirectional"))
      (node (ref "U$30") (pin "B3") (pinfunction "AGND_B3") (pintype "bidirectional"))
      (node (ref "U$30") (pin "B4") (pinfunction "AGND_B4") (pintype "bidirectional"))
      (node (ref "U$30") (pin "C3") (pinfunction "AGND_C3") (pintype "bidirectional"))
      (node (ref "U$30") (pin "C4") (pinfunction "AGND_C4") (pintype "bidirectional"))
      (node (ref "U$30") (pin "C5") (pinfunction "DGND_C5") (pintype "bidirectional"))
      (node (ref "U$30") (pin "D4") (pinfunction "AGND_D4") (pintype "bidirectional"))
      (node (ref "U$39") (pin "4") (pinfunction "TRIG_4") (pintype "bidirectional"))
      (node (ref "U$39") (pin "8") (pinfunction "GND_8") (pintype "bidirectional"))
      (node (ref "U$39") (pin "9") (pinfunction "GND_9") (pintype "bidirectional"))
      (node (ref "U$6") (pin "2") (pinfunction "GND_2") (pintype "bidirectional"))
      (node (ref "U1") (pin "3") (pinfunction "GND_3") (pintype "power_in"))
      (node (ref "U4") (pin "23") (pinfunction "GND_2_23") (pintype "power_in"))
      (node (ref "U4") (pin "24") (pinfunction "PD_GND_24") (pintype "passive"))
      (node (ref "U4") (pin "29") (pinfunction "PGND_29") (pintype "power_in"))
      (node (ref "U4") (pin "30") (pinfunction "GND_3_30") (pintype "power_in"))
      (node (ref "U4") (pin "31") (pinfunction "GND_4_31") (pintype "power_in"))
      (node (ref "U4") (pin "32") (pinfunction "GND_32") (pintype "power_in"))
      (node (ref "U4") (pin "33") (pinfunction "VSS_33") (pintype "power_in"))
      (node (ref "U4") (pin "7") (pinfunction "VSS_2_7") (pintype "power_in"))
      (node (ref "U6") (pin "2") (pinfunction "GND_2") (pintype "passive"))
    )
    (net (code "14") (name "HR_INT") (class "Default")
      (node (ref "D13") (pin "2") (pinfunction "2_2") (pintype "bidirectional"))
      (node (ref "J2") (pin "14") (pinfunction "14_14") (pintype "passive"))
      (node (ref "JP1") (pin "2") (pinfunction "P$2_2") (pintype "bidirectional"))
      (node (ref "R11") (pin "2") (pinfunction "2_2") (pintype "passive"))
      (node (ref "U$3") (pin "18") (pinfunction "HR_INT_18") (pintype "bidirectional"))
    )
    (net (code "15") (name "IN3_4") (class "Default")
      (node (ref "U6") (pin "6") (pinfunction "IN_3-4_6") (pintype "bidirectional"))
    )
    (net (code "16") (name "INT") (class "Default")
      (node (ref "R22") (pin "1") (pinfunction "1_1") (pintype "passive"))
      (node (ref "U$39") (pin "5") (pinfunction "INT1_5") (pintype "bidirectional"))
      (node (ref "U4") (pin "13") (pinfunction "P0.2_13") (pintype "passive"))
    )
    (net (code "17") (name "INTB") (class "Default")
      (node (ref "J1") (pin "8") (pinfunction "8_8") (pintype "passive"))
      (node (ref "U$30") (pin "D2") (pinfunction "INTB_D2") (pintype "bidirectional"))
    )
    (net (code "18") (name "MFIO") (class "Default")
      (node (ref "Q3") (pin "2") (pinfunction "S_2") (pintype "passive"))
      (node (ref "R17") (pin "2") (pinfunction "2_2") (pintype "passive"))
      (node (ref "R20") (pin "2") (pinfunction "2_2") (pintype "passive"))
      (node (ref "U$3") (pin "1") (pinfunction "MFIO_1") (pintype "bidirectional"))
    )
    (net (code "19") (name "MFIO_IN") (class "Default")
      (node (ref "J1") (pin "6") (pinfunction "6_6") (pintype "passive"))
      (node (ref "Q3") (pin "3") (pinfunction "D_3") (pintype "passive"))
      (node (ref "R18") (pin "2") (pinfunction "2_2") (pintype "passive"))
    )
    (net (code "20") (name "MISO") (class "Default")
      (node (ref "J1") (pin "5") (pinfunction "5_5") (pintype "passive"))
      (node (ref "U$30") (pin "E3") (pinfunction "SDO_E3") (pintype "bidirectional"))
    )
    (net (code "21") (name "MOSI") (class "Default")
      (node (ref "J1") (pin "14") (pinfunction "14_14") (pintype "passive"))
      (node (ref "U$30") (pin "E4") (pinfunction "SDI_E4") (pintype "bidirectional"))
    )
    (net (code "22") (name "NO1") (class "Default")
      (node (ref "D4") (pin "C1") (pinfunction "C_C1") (pintype "passive"))
      (node (ref "D4") (pin "C2") (pinfunction "C_C2") (pintype "passive"))
      (node (ref "U4") (pin "21") (pinfunction "LED1_DRV_21") (pintype "output"))
      (node (ref "U6") (pin "11") (pinfunction "NO1_11") (pintype "bidirectional"))
    )
    (net (code "23") (name "Net-(C7-Pad2)") (class "Default")
      (node (ref "C7") (pin "2") (pinfunction "2_2") (pintype "passive"))
      (node (ref "R8") (pin "1") (pinfunction "1_1") (pintype "passive"))
    )
    (net (code "24") (name "Net-(C36-Pad2)") (class "Default")
      (node (ref "C36") (pin "2") (pinfunction "2_2") (pintype "passive"))
      (node (ref "R25") (pin "2") (pinfunction "2_2") (pintype "passive"))
    )
    (net (code "25") (name "Net-(C63-Pad1)") (class "Default")
      (node (ref "C63") (pin "1") (pinfunction "1_1") (pintype "passive"))
      (node (ref "R10") (pin "1") (pinfunction "1_1") (pintype "passive"))
    )
    (net (code "26") (name "Net-(C66-Pad1)") (class "Default")
      (node (ref "C66") (pin "1") (pinfunction "1_1") (pintype "passive"))
      (node (ref "R9") (pin "2") (pinfunction "2_2") (pintype "passive"))
    )
    (net (code "27") (name "Net-(LED1-IRC)") (class "Default")
      (node (ref "LED1") (pin "4") (pinfunction "IRC_4") (pintype "passive"))
      (node (ref "U6") (pin "13") (pinfunction "NC1_13") (pintype "bidirectional"))
    )
    (net (code "28") (name "Net-(LED1-RC)") (class "Default")
      (node (ref "LED1") (pin "2") (pinfunction "RC_2") (pintype "passive"))
      (node (ref "U6") (pin "1") (pinfunction "NC2_1") (pintype "bidirectional"))
    )
    (net (code "29") (name "Net-(R10-Pad2)") (class "Default")
      (node (ref "R10") (pin "2") (pinfunction "2_2") (pintype "passive"))
      (node (ref "R43") (pin "1") (pinfunction "1_1") (pintype "passive"))
      (node (ref "TP2") (pin "TP") (pinfunction "TP_TP") (pintype "input"))
    )
    (net (code "30") (name "Net-(R42-Pad1)") (class "Default")
      (node (ref "R42") (pin "1") (pinfunction "1_1") (pintype "passive"))
      (node (ref "R9") (pin "1") (pinfunction "1_1") (pintype "passive"))
      (node (ref "TP1") (pin "TP") (pinfunction "TP_TP") (pintype "input"))
    )
    (net (code "31") (name "Net-(U$3-VCORE)") (class "Default")
      (node (ref "C4") (pin "1") (pinfunction "1_1") (pintype "passive"))
      (node (ref "U$3") (pin "12") (pinfunction "VCORE_12") (pintype "bidirectional"))
    )
    (net (code "32") (name "Net-(U$10-1)") (class "Default")
      (node (ref "C5") (pin "1") (pinfunction "1_1") (pintype "passive"))
      (node (ref "U$10") (pin "P$1") (pinfunction "1_P$1") (pintype "passive"))
      (node (ref "U$3") (pin "9") (pinfunction "32KIN_9") (pintype "bidirectional"))
    )
    (net (code "33") (name "Net-(U$10-2)") (class "Default")
      (node (ref "C6") (pin "2") (pinfunction "2_2") (pintype "passive"))
      (node (ref "U$10") (pin "P$2") (pinfunction "2_P$2") (pintype "passive"))
      (node (ref "U$3") (pin "8") (pinfunction "32KOUT_8") (pintype "bidirectional"))
    )
    (net (code "34") (name "Net-(U$30-BIN)") (class "Default")
      (node (ref "C67") (pin "1") (pinfunction "1_1") (pintype "passive"))
      (node (ref "C69") (pin "1") (pinfunction "1_1") (pintype "passive"))
      (node (ref "R42") (pin "2") (pinfunction "2_2") (pintype "passive"))
      (node (ref "U$30") (pin "A3") (pinfunction "BIN_A3") (pintype "bidirectional"))
    )
    (net (code "35") (name "Net-(U$30-BIP)") (class "Default")
      (node (ref "C68") (pin "1") (pinfunction "1_1") (pintype "passive"))
      (node (ref "C69") (pin "2") (pinfunction "2_2") (pintype "passive"))
      (node (ref "R43") (pin "2") (pinfunction "2_2") (pintype "passive"))
      (node (ref "U$30") (pin "A4") (pinfunction "BIP_A4") (pintype "bidirectional"))
    )
    (net (code "36") (name "Net-(U$30-CAPN)") (class "Default")
      (node (ref "C26") (pin "2") (pinfunction "2_2") (pintype "passive"))
      (node (ref "U$30") (pin "B5") (pinfunction "CAPN_B5") (pintype "bidirectional"))
    )
    (net (code "37") (name "Net-(U$30-CAPP)") (class "Default")
      (node (ref "C26") (pin "1") (pinfunction "1_1") (pintype "passive"))
      (node (ref "U$30") (pin "B6") (pinfunction "CAPP_B6") (pintype "bidirectional"))
    )
    (net (code "38") (name "Net-(U$30-CPLL)") (class "Default")
      (node (ref "C29") (pin "1") (pinfunction "1_1") (pintype "passive"))
      (node (ref "U$30") (pin "C6") (pinfunction "CPLL_C6") (pintype "bidirectional"))
    )
    (net (code "39") (name "Net-(U$30-DRVN)") (class "Default")
      (node (ref "C66") (pin "2") (pinfunction "2_2") (pintype "passive"))
      (node (ref "U$30") (pin "A2") (pinfunction "DRVN_A2") (pintype "bidirectional"))
    )
    (net (code "40") (name "Net-(U$30-DRVP)") (class "Default")
      (node (ref "C63") (pin "2") (pinfunction "2_2") (pintype "passive"))
      (node (ref "U$30") (pin "A1") (pinfunction "DRVP_A1") (pintype "bidirectional"))
    )
    (net (code "41") (name "Net-(U$30-RBIAS)") (class "Default")
      (node (ref "R44") (pin "1") (pinfunction "1_1") (pintype "passive"))
      (node (ref "U$30") (pin "B2") (pinfunction "RBIAS_B2") (pintype "bidirectional"))
    )
    (net (code "42") (name "Net-(U$30-VBG)") (class "Default")
      (node (ref "C34") (pin "1") (pinfunction "1_1") (pintype "passive"))
      (node (ref "U$30") (pin "B1") (pinfunction "VBG_B1") (pintype "bidirectional"))
    )
    (net (code "43") (name "Net-(U$30-VREF)") (class "Default")
      (node (ref "C32") (pin "1") (pinfunction "1_1") (pintype "passive"))
      (node (ref "U$30") (pin "D1") (pinfunction "VREF_D1") (pintype "bidirectional"))
    )
    (net (code "44") (name "Net-(U$32-1)") (class "Default")
      (node (ref "C17") (pin "1") (pinfunction "1_1") (pintype "passive"))
      (node (ref "U$32") (pin "P$1") (pinfunction "1_P$1") (pintype "passive"))
      (node (ref "U4") (pin "9") (pinfunction "32KOUT_9") (pintype "output"))
    )
    (net (code "45") (name "Net-(U$32-2)") (class "Default")
      (node (ref "C18") (pin "2") (pinfunction "2_2") (pintype "passive"))
      (node (ref "U$32") (pin "P$2") (pinfunction "2_P$2") (pintype "passive"))
      (node (ref "U4") (pin "8") (pinfunction "32KIN_8") (pintype "input"))
    )
    (net (code "46") (name "Net-(U1-LX)") (class "Default")
      (node (ref "L1") (pin "2") (pinfunction "2_2") (pintype "passive"))
      (node (ref "U1") (pin "2") (pinfunction "LX_2") (pintype "bidirectional"))
    )
    (net (code "47") (name "Net-(U1-SEL)") (class "Default")
      (node (ref "R14") (pin "2") (pinfunction "2_2") (pintype "passive"))
      (node (ref "U1") (pin "4") (pinfunction "SEL_4") (pintype "bidirectional"))
    )
    (net (code "48") (name "Net-(U4-P0.3)") (class "Default")
      (node (ref "R21") (pin "1") (pinfunction "1_1") (pintype "passive"))
      (node (ref "U4") (pin "38") (pinfunction "P0.3_38") (pintype "input"))
    )
    (net (code "49") (name "Net-(U4-PD2_CAT)") (class "Default")
      (node (ref "U4") (pin "25") (pinfunction "PD2_IN_25") (pintype "input"))
      (node (ref "U4") (pin "26") (pinfunction "PD2_CAT_26") (pintype "passive"))
    )
    (net (code "50") (name "Net-(U4-VCORE)") (class "Default")
      (node (ref "C28") (pin "1") (pinfunction "1_1") (pintype "passive"))
      (node (ref "U4") (pin "5") (pinfunction "VCORE_5") (pintype "power_in"))
    )
    (net (code "51") (name "Net-(U4-VREF)") (class "Default")
      (node (ref "C37") (pin "2") (pinfunction "2_2") (pintype "passive"))
      (node (ref "U4") (pin "2") (pinfunction "VREF_2") (pintype "passive"))
    )
    (net (code "52") (name "Net-(U6-NO2)") (class "Default")
      (node (ref "D3") (pin "C1") (pinfunction "C_C1") (pintype "passive"))
      (node (ref "D3") (pin "C2") (pinfunction "C_C2") (pintype "passive"))
      (node (ref "U6") (pin "15") (pinfunction "NO2_15") (pintype "bidirectional"))
    )
    (net (code "53") (name "RESET") (class "Default")
      (node (ref "C7") (pin "1") (pinfunction "1_1") (pintype "passive"))
      (node (ref "Q4") (pin "2") (pinfunction "S_2") (pintype "passive"))
      (node (ref "R1") (pin "2") (pinfunction "2_2") (pintype "passive"))
      (node (ref "U$3") (pin "6") (pinfunction "RSTN_6") (pintype "bidirectional"))
    )
    (net (code "54") (name "RESET1_IN") (class "Default")
      (node (ref "J1") (pin "2") (pinfunction "2_2") (pintype "passive"))
      (node (ref "Q5") (pin "3") (pinfunction "D_3") (pintype "passive"))
      (node (ref "R19") (pin "2") (pinfunction "2_2") (pintype "passive"))
    )
    (net (code "55") (name "RESET_1") (class "Default")
      (node (ref "C36") (pin "1") (pinfunction "1_1") (pintype "passive"))
      (node (ref "Q5") (pin "2") (pinfunction "S_2") (pintype "passive"))
      (node (ref "R7") (pin "2") (pinfunction "2_2") (pintype "passive"))
      (node (ref "U4") (pin "10") (pinfunction "RSTN_10") (pintype "input"))
    )
    (net (code "56") (name "RESET_IN") (class "Default")
      (node (ref "J1") (pin "1") (pinfunction "1_1") (pintype "passive"))
      (node (ref "Q4") (pin "3") (pinfunction "D_3") (pintype "passive"))
      (node (ref "R2") (pin "2") (pinfunction "2_2") (pintype "passive"))
    )
    (net (code "57") (name "SCK") (class "Default")
      (node (ref "J1") (pin "18") (pinfunction "18_18") (pintype "passive"))
      (node (ref "U$30") (pin "E5") (pinfunction "SCLK_E5") (pintype "bidirectional"))
    )
    (net (code "58") (name "SCL") (class "Default")
      (node (ref "Q1") (pin "2") (pinfunction "S_2") (pintype "passive"))
      (node (ref "R12") (pin "2") (pinfunction "2_2") (pintype "passive"))
      (node (ref "R3") (pin "2") (pinfunction "2_2") (pintype "passive"))
      (node (ref "U$3") (pin "24") (pinfunction "SLAVE_SCL_24") (pintype "bidirectional"))
      (node (ref "U4") (pin "3") (pinfunction "P0.8_3") (pintype "passive"))
    )
    (net (code "59") (name "SCL_IN") (class "Default")
      (node (ref "J1") (pin "4") (pinfunction "4_4") (pintype "passive"))
      (node (ref "Q1") (pin "3") (pinfunction "D_3") (pintype "passive"))
      (node (ref "R13") (pin "2") (pinfunction "2_2") (pintype "passive"))
    )
    (net (code "60") (name "SDA") (class "Default")
      (node (ref "Q2") (pin "2") (pinfunction "S_2") (pintype "passive"))
      (node (ref "R15") (pin "2") (pinfunction "2_2") (pintype "passive"))
      (node (ref "R4") (pin "2") (pinfunction "2_2") (pintype "passive"))
      (node (ref "U$3") (pin "23") (pinfunction "SLAVE_SDA_23") (pintype "bidirectional"))
      (node (ref "U4") (pin "4") (pinfunction "P0.9_4") (pintype "passive"))
    )
    (net (code "61") (name "SDA_IN") (class "Default")
      (node (ref "J1") (pin "3") (pinfunction "3_3") (pintype "passive"))
      (node (ref "Q2") (pin "3") (pinfunction "D_3") (pintype "passive"))
      (node (ref "R16") (pin "2") (pinfunction "2_2") (pintype "passive"))
    )
    (net (code "62") (name "SDI") (class "Default")
      (node (ref "U$39") (pin "2") (pinfunction "SDI/SDA_2") (pintype "bidirectional"))
      (node (ref "U4") (pin "36") (pinfunction "P0.5_36") (pintype "bidirectional"))
    )
    (net (code "63") (name "SDO") (class "Default")
      (node (ref "U$39") (pin "1") (pinfunction "SDO/ADDR_1") (pintype "bidirectional"))
      (node (ref "U4") (pin "37") (pinfunction "P0.4_37") (pintype "bidirectional"))
    )
    (net (code "64") (name "SEN_CS") (class "Default")
      (node (ref "U$39") (pin "10") (pinfunction "NCS_10") (pintype "bidirectional"))
      (node (ref "U4") (pin "11") (pinfunction "P0.0_11") (pintype "passive"))
    )
    (net (code "65") (name "SEN_SCK") (class "Default")
      (node (ref "U$39") (pin "12") (pinfunction "SCLK/SCL_12") (pintype "bidirectional"))
      (node (ref "U4") (pin "35") (pinfunction "P0.6_35") (pintype "bidirectional"))
    )
    (net (code "66") (name "S_SCL") (class "Default")
      (node (ref "D2") (pin "2") (pinfunction "2_2") (pintype "bidirectional"))
      (node (ref "J2") (pin "16") (pinfunction "16_16") (pintype "passive"))
      (node (ref "JP1") (pin "4") (pinfunction "P$4_4") (pintype "bidirectional"))
      (node (ref "R5") (pin "2") (pinfunction "2_2") (pintype "passive"))
      (node (ref "U$3") (pin "14") (pinfunction "SENSOR_SCL_14") (pintype "bidirectional"))
    )
    (net (code "67") (name "S_SDA") (class "Default")
      (node (ref "D1") (pin "2") (pinfunction "2_2") (pintype "bidirectional"))
      (node (ref "J2") (pin "18") (pinfunction "18_18") (pintype "passive"))
      (node (ref "JP1") (pin "3") (pinfunction "P$3_3") (pintype "bidirectional"))
      (node (ref "R6") (pin "2") (pinfunction "2_2") (pintype "passive"))
      (node (ref "U$3") (pin "13") (pinfunction "SENSOR_SDA_13") (pintype "bidirectional"))
    )
    (net (code "68") (name "VBAT") (class "Default")
      (node (ref "C10") (pin "1") (pinfunction "1_1") (pintype "passive"))
      (node (ref "C19") (pin "1") (pinfunction "1_1") (pintype "passive"))
      (node (ref "J2") (pin "15") (pinfunction "15_15") (pintype "passive"))
      (node (ref "L1") (pin "1") (pinfunction "1_1") (pintype "passive"))
      (node (ref "U$6") (pin "1") (pinfunction "VIN_1") (pintype "bidirectional"))
      (node (ref "U$6") (pin "3") (pinfunction "EN_3") (pintype "bidirectional"))
      (node (ref "U1") (pin "5") (pinfunction "IN_5") (pintype "input"))
      (node (ref "U1") (pin "6") (pinfunction "EN_6") (pintype "bidirectional"))
    )
    (net (code "69") (name "VSENSE") (class "Default")
      (node (ref "C27") (pin "1") (pinfunction "1_1") (pintype "passive"))
      (node (ref "C38") (pin "1") (pinfunction "1_1") (pintype "passive"))
      (node (ref "C39") (pin "1") (pinfunction "1_1") (pintype "passive"))
      (node (ref "C40") (pin "1") (pinfunction "1_1") (pintype "passive"))
      (node (ref "C41") (pin "1") (pinfunction "1_1") (pintype "passive"))
      (node (ref "C42") (pin "1") (pinfunction "1_1") (pintype "passive"))
      (node (ref "C48") (pin "1") (pinfunction "1_1") (pintype "passive"))
      (node (ref "C9") (pin "1") (pinfunction "1_1") (pintype "passive"))
      (node (ref "D3") (pin "A") (pinfunction "A_A") (pintype "passive"))
      (node (ref "D4") (pin "A") (pinfunction "A_A") (pintype "passive"))
      (node (ref "J2") (pin "17") (pinfunction "17_17") (pintype "passive"))
      (node (ref "J2") (pin "19") (pinfunction "19_19") (pintype "passive"))
      (node (ref "JP1") (pin "1") (pinfunction "P$1_1") (pintype "bidirectional"))
      (node (ref "LED1") (pin "3") (pinfunction "A_3") (pintype "passive"))
      (node (ref "U1") (pin "1") (pinfunction "OUT_1") (pintype "output"))
      (node (ref "U4") (pin "18") (pinfunction "VLED_18") (pintype "input"))
      (node (ref "U6") (pin "10") (pinfunction "V+_10") (pintype "power_in"))
    )
    (net (code "70") (name "W_MFIO") (class "Default")
      (node (ref "J1") (pin "10") (pinfunction "10_10") (pintype "passive"))
      (node (ref "R20") (pin "1") (pinfunction "1_1") (pintype "passive"))
      (node (ref "U4") (pin "12") (pinfunction "P0.1_12") (pintype "passive"))
    )
    (net (code "71") (name "unconnected-(J1-Pad7)") (class "Default")
      (node (ref "J1") (pin "7") (pinfunction "7_7") (pintype "passive"))
    )
    (net (code "72") (name "unconnected-(J1-Pad12)") (class "Default")
      (node (ref "J1") (pin "12") (pinfunction "12_12") (pintype "passive"))
    )
    (net (code "73") (name "unconnected-(J1-Pad13)") (class "Default")
      (node (ref "J1") (pin "13") (pinfunction "13_13") (pintype "passive"))
    )
    (net (code "74") (name "unconnected-(J1-Pad16)") (class "Default")
      (node (ref "J1") (pin "16") (pinfunction "16_16") (pintype "passive"))
    )
    (net (code "75") (name "unconnected-(J2-Pad3)") (class "Default")
      (node (ref "J2") (pin "3") (pinfunction "3_3") (pintype "passive"))
    )
    (net (code "76") (name "unconnected-(J2-Pad4)") (class "Default")
      (node (ref "J2") (pin "4") (pinfunction "4_4") (pintype "passive"))
    )
    (net (code "77") (name "unconnected-(J2-Pad5)") (class "Default")
      (node (ref "J2") (pin "5") (pinfunction "5_5") (pintype "passive"))
    )
    (net (code "78") (name "unconnected-(J2-Pad6)") (class "Default")
      (node (ref "J2") (pin "6") (pinfunction "6_6") (pintype "passive"))
    )
    (net (code "79") (name "unconnected-(J2-Pad7)") (class "Default")
      (node (ref "J2") (pin "7") (pinfunction "7_7") (pintype "passive"))
    )
    (net (code "80") (name "unconnected-(J2-Pad8)") (class "Default")
      (node (ref "J2") (pin "8") (pinfunction "8_8") (pintype "passive"))
    )
    (net (code "81") (name "unconnected-(J2-Pad9)") (class "Default")
      (node (ref "J2") (pin "9") (pinfunction "9_9") (pintype "passive"))
    )
    (net (code "82") (name "unconnected-(J2-Pad10)") (class "Default")
      (node (ref "J2") (pin "10") (pinfunction "10_10") (pintype "passive"))
    )
    (net (code "83") (name "unconnected-(J2-Pad11)") (class "Default")
      (node (ref "J2") (pin "11") (pinfunction "11_11") (pintype "passive"))
    )
    (net (code "84") (name "unconnected-(J2-Pad12)") (class "Default")
      (node (ref "J2") (pin "12") (pinfunction "12_12") (pintype "passive"))
    )
    (net (code "85") (name "unconnected-(J2-Pad13)") (class "Default")
      (node (ref "J2") (pin "13") (pinfunction "13_13") (pintype "passive"))
    )
    (net (code "86") (name "unconnected-(U$3-ACCL_INT-Pad19)") (class "Default")
      (node (ref "U$3") (pin "19") (pinfunction "ACCL_INT_19") (pintype "bidirectional"))
    )
    (net (code "87") (name "unconnected-(U$3-D.N.C-Pad2)") (class "Default")
      (node (ref "U$3") (pin "2") (pinfunction "D.N.C_2") (pintype "bidirectional"))
    )
    (net (code "88") (name "unconnected-(U$3-D.N.C-Pad4)") (class "Default")
      (node (ref "U$3") (pin "4") (pinfunction "D.N.C_4") (pintype "bidirectional"))
    )
    (net (code "89") (name "unconnected-(U$3-D.N.C-Pad5)") (class "Default")
      (node (ref "U$3") (pin "5") (pinfunction "D.N.C_5") (pintype "bidirectional"))
    )
    (net (code "90") (name "unconnected-(U$3-D.N.C-Pad16)") (class "Default")
      (node (ref "U$3") (pin "16") (pinfunction "D.N.C_16") (pintype "bidirectional"))
    )
    (net (code "91") (name "unconnected-(U$3-D.N.C-Pad17)") (class "Default")
      (node (ref "U$3") (pin "17") (pinfunction "D.N.C_17") (pintype "bidirectional"))
    )
    (net (code "92") (name "unconnected-(U$3-D.N.C-Pad20)") (class "Default")
      (node (ref "U$3") (pin "20") (pinfunction "D.N.C_20") (pintype "bidirectional"))
    )
    (net (code "93") (name "unconnected-(U$3-D.N.C-Pad21)") (class "Default")
      (node (ref "U$3") (pin "21") (pinfunction "D.N.C_21") (pintype "bidirectional"))
    )
    (net (code "94") (name "unconnected-(U$3-N.C-Pad3)") (class "Default")
      (node (ref "U$3") (pin "3") (pinfunction "N.C_3") (pintype "bidirectional"))
    )
    (net (code "95") (name "unconnected-(U$3-N.C-Pad15)") (class "Default")
      (node (ref "U$3") (pin "15") (pinfunction "N.C_15") (pintype "bidirectional"))
    )
    (net (code "96") (name "unconnected-(U$6-NC-Pad4)") (class "Default")
      (node (ref "U$6") (pin "4") (pinfunction "NC_4") (pintype "bidirectional"))
    )
    (net (code "97") (name "unconnected-(U$29-NC-Pad1)") (class "Default")
      (node (ref "U$29") (pin "1") (pinfunction "NC_1") (pintype "bidirectional"))
    )
    (net (code "98") (name "unconnected-(U$30-AOUT-PadC2)") (class "Default")
      (node (ref "U$30") (pin "C2") (pinfunction "AOUT_C2") (pintype "bidirectional"))
    )
    (net (code "99") (name "unconnected-(U$30-INT2B-PadE2)") (class "Default")
      (node (ref "U$30") (pin "E2") (pinfunction "INT2B_E2") (pintype "bidirectional"))
    )
    (net (code "100") (name "unconnected-(U$39-INT2-Pad6)") (class "Default")
      (node (ref "U$39") (pin "6") (pinfunction "INT2_6") (pintype "bidirectional"))
    )
    (net (code "101") (name "unconnected-(U$39-NC-Pad11)") (class "Default")
      (node (ref "U$39") (pin "11") (pinfunction "NC_11") (pintype "bidirectional"))
    )
    (net (code "102") (name "unconnected-(U4-NC-Pad34)") (class "Default")
      (node (ref "U4") (pin "34") (pinfunction "NC_34") (pintype "passive"))
    )
    (net (code "103") (name "unconnected-(U4-NC_2-Pad14)") (class "Default")
      (node (ref "U4") (pin "14") (pinfunction "NC_2_14") (pintype "passive"))
    )
    (net (code "104") (name "unconnected-(U4-NC_3-Pad15)") (class "Default")
      (node (ref "U4") (pin "15") (pinfunction "NC_3_15") (pintype "passive"))
    )
    (net (code "105") (name "unconnected-(U4-NC_4-Pad16)") (class "Default")
      (node (ref "U4") (pin "16") (pinfunction "NC_4_16") (pintype "passive"))
    )
    (net (code "106") (name "unconnected-(U4-NC_5-Pad17)") (class "Default")
      (node (ref "U4") (pin "17") (pinfunction "NC_5_17") (pintype "passive"))
    )
    (net (code "107") (name "unconnected-(U4-NC_6-Pad27)") (class "Default")
      (node (ref "U4") (pin "27") (pinfunction "NC_6_27") (pintype "passive"))
    )
    (net (code "108") (name "unconnected-(U4-PD1_IN-Pad1)") (class "Default")
      (node (ref "U4") (pin "1") (pinfunction "PD1_IN_1") (pintype "input"))
    )
    (net (code "109") (name "unconnected-(U6-COM3-Pad4)") (class "Default")
      (node (ref "U6") (pin "4") (pinfunction "COM3_4") (pintype "bidirectional"))
    )
    (net (code "110") (name "unconnected-(U6-COM4-Pad8)") (class "Default")
      (node (ref "U6") (pin "8") (pinfunction "COM4_8") (pintype "bidirectional"))
    )
    (net (code "111") (name "unconnected-(U6-NC3-Pad5)") (class "Default")
      (node (ref "U6") (pin "5") (pinfunction "NC3_5") (pintype "bidirectional"))
    )
    (net (code "112") (name "unconnected-(U6-NC4-Pad9)") (class "Default")
      (node (ref "U6") (pin "9") (pinfunction "NC4_9") (pintype "bidirectional"))
    )
    (net (code "113") (name "unconnected-(U6-NO3-Pad3)") (class "Default")
      (node (ref "U6") (pin "3") (pinfunction "NO3_3") (pintype "bidirectional"))
    )
    (net (code "114") (name "unconnected-(U6-NO4-Pad7)") (class "Default")
      (node (ref "U6") (pin "7") (pinfunction "NO4_7") (pintype "bidirectional"))
    )
  )
)
